# Exposure_Timer.net
KiCad netlist of a schematic drawn in EAGLE
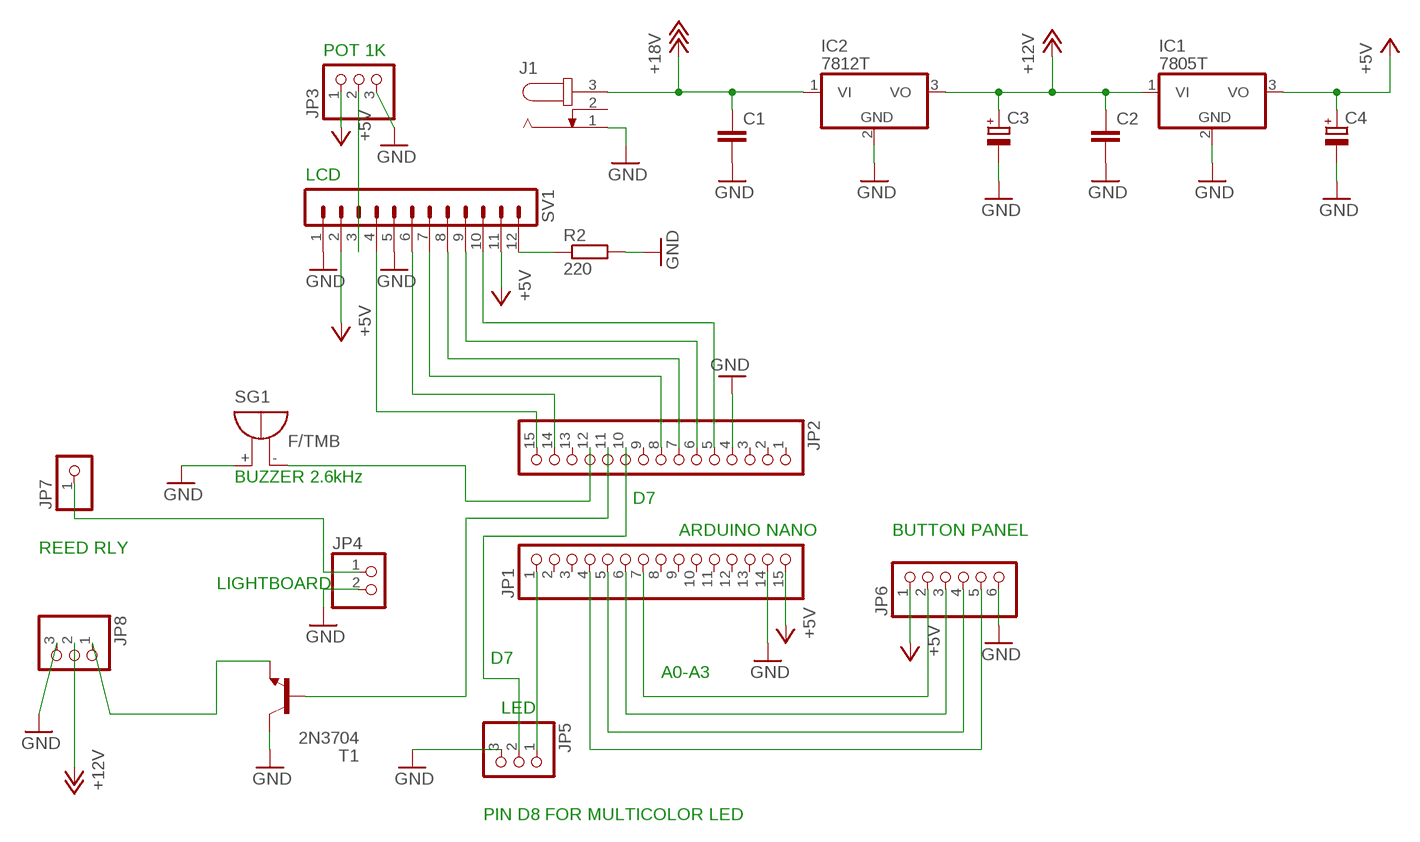
[diagram p0: schematic, sheet 1]

(export (version "E")
  (design (tool "Eeschema 10.0.6"))
  (components
    (comp (ref "C1")
      (value "C-EU025-030X050")
      (footprint "eagle-import:C025-030X050")
      (libsource (lib "eagle-import") (part "C-EU025-030X050"))
    )
    (comp (ref "C2")
      (value "C-EU025-030X050")
      (footprint "eagle-import:C025-030X050")
      (libsource (lib "eagle-import") (part "C-EU025-030X050"))
    )
    (comp (ref "C3")
      (value "CPOL-EUE2,5-6E")
      (footprint "eagle-import:E2,5-6E")
      (libsource (lib "eagle-import") (part "CPOL-EUE2,5-6E"))
    )
    (comp (ref "C4")
      (value "CPOL-EUE2,5-6E")
      (footprint "eagle-import:E2,5-6E")
      (libsource (lib "eagle-import") (part "CPOL-EUE2,5-6E"))
    )
    (comp (ref "IC1")
      (value "7805T")
      (footprint "eagle-import:TO220H")
      (libsource (lib "eagle-import") (part "78T05"))
    )
    (comp (ref "IC2")
      (value "7812T")
      (footprint "eagle-import:TO220H")
      (libsource (lib "eagle-import") (part "78T12"))
    )
    (comp (ref "J1")
      (value "JACK-PLUG1")
      (footprint "eagle-import:SPC4078")
      (libsource (lib "eagle-import") (part "JACK-PLUG1"))
    )
    (comp (ref "JP1")
      (value "PINHD-1X15")
      (footprint "eagle-import:1X15")
      (libsource (lib "eagle-import") (part "PINHD-1X15"))
    )
    (comp (ref "JP2")
      (value "PINHD-1X15")
      (footprint "eagle-import:1X15")
      (libsource (lib "eagle-import") (part "PINHD-1X15"))
    )
    (comp (ref "JP3")
      (value "PINHD-1X3")
      (footprint "eagle-import:1X03")
      (libsource (lib "eagle-import") (part "PINHD-1X3"))
    )
    (comp (ref "JP4")
      (value "PINHD-1X2")
      (footprint "eagle-import:1X02")
      (libsource (lib "eagle-import") (part "PINHD-1X2"))
    )
    (comp (ref "JP5")
      (value "PINHD-1X3")
      (footprint "eagle-import:1X03")
      (libsource (lib "eagle-import") (part "PINHD-1X3"))
    )
    (comp (ref "JP6")
      (value "PINHD-1X6")
      (footprint "eagle-import:1X06")
      (libsource (lib "eagle-import") (part "PINHD-1X6"))
    )
    (comp (ref "JP7")
      (value "PINHD-1X1")
      (footprint "eagle-import:1X01")
      (libsource (lib "eagle-import") (part "PINHD-1X1"))
    )
    (comp (ref "JP8")
      (value "PINHD-1X3")
      (footprint "eagle-import:1X03")
      (libsource (lib "eagle-import") (part "PINHD-1X3"))
    )
    (comp (ref "R2")
      (value "220")
      (footprint "eagle-import:0204_7")
      (libsource (lib "eagle-import") (part "R-EU_0204/7"))
    )
    (comp (ref "SG1")
      (value "F/TMB")
      (footprint "eagle-import:F_TMB")
      (libsource (lib "eagle-import") (part "F/TMB"))
    )
    (comp (ref "SV1")
      (value "MA12-1")
      (footprint "eagle-import:MA12-1")
      (libsource (lib "eagle-import") (part "MA12-1"))
    )
    (comp (ref "T1")
      (value "2N3704")
      (footprint "eagle-import:TO92")
      (libsource (lib "eagle-import") (part "2N3704"))
    )
  )
  (nets
    (net (code "1") (name "+5V") (class "Default")
      (node (ref "C4") (pin "+") (pinfunction "+_+") (pintype "passive"))
      (node (ref "IC1") (pin "3") (pinfunction "VO_3") (pintype "passive"))
      (node (ref "JP1") (pin "15") (pinfunction "15_15") (pintype "passive"))
      (node (ref "JP3") (pin "1") (pinfunction "1_1") (pintype "passive"))
      (node (ref "JP6") (pin "1") (pinfunction "1_1") (pintype "passive"))
      (node (ref "SV1") (pin "11") (pinfunction "11_11") (pintype "passive"))
      (node (ref "SV1") (pin "2") (pinfunction "2_2") (pintype "passive"))
    )
    (net (code "2") (name "+12V") (class "Default")
      (node (ref "C2") (pin "1") (pinfunction "1_1") (pintype "passive"))
      (node (ref "C3") (pin "+") (pinfunction "+_+") (pintype "passive"))
      (node (ref "IC1") (pin "1") (pinfunction "VI_1") (pintype "input"))
      (node (ref "IC2") (pin "3") (pinfunction "VO_3") (pintype "passive"))
      (node (ref "JP8") (pin "2") (pinfunction "2_2") (pintype "passive"))
    )
    (net (code "3") (name "+18V") (class "Default")
      (node (ref "C1") (pin "1") (pinfunction "1_1") (pintype "passive"))
      (node (ref "IC2") (pin "1") (pinfunction "VI_1") (pintype "input"))
      (node (ref "J1") (pin "3") (pinfunction "3_3") (pintype "passive"))
    )
    (net (code "4") (name "GND") (class "Default")
      (node (ref "C1") (pin "2") (pinfunction "2_2") (pintype "passive"))
      (node (ref "C2") (pin "2") (pinfunction "2_2") (pintype "passive"))
      (node (ref "C3") (pin "-") (pinfunction "-_-") (pintype "passive"))
      (node (ref "C4") (pin "-") (pinfunction "-_-") (pintype "passive"))
      (node (ref "IC1") (pin "2") (pinfunction "GND_2") (pintype "passive"))
      (node (ref "IC2") (pin "2") (pinfunction "GND_2") (pintype "passive"))
      (node (ref "J1") (pin "1") (pinfunction "1_1") (pintype "passive"))
      (node (ref "JP1") (pin "14") (pinfunction "14_14") (pintype "passive"))
      (node (ref "JP2") (pin "4") (pinfunction "4_4") (pintype "passive"))
      (node (ref "JP3") (pin "3") (pinfunction "3_3") (pintype "passive"))
      (node (ref "JP4") (pin "2") (pinfunction "2_2") (pintype "passive"))
      (node (ref "JP5") (pin "3") (pinfunction "3_3") (pintype "passive"))
      (node (ref "JP6") (pin "6") (pinfunction "6_6") (pintype "passive"))
      (node (ref "JP8") (pin "3") (pinfunction "3_3") (pintype "passive"))
      (node (ref "R2") (pin "2") (pinfunction "2_2") (pintype "passive"))
      (node (ref "SG1") (pin "+") (pinfunction "+_+") (pintype "passive"))
      (node (ref "SV1") (pin "1") (pinfunction "1_1") (pintype "passive"))
      (node (ref "SV1") (pin "5") (pinfunction "5_5") (pintype "passive"))
      (node (ref "T1") (pin "2") (pinfunction "C_2") (pintype "passive"))
    )
    (net (code "5") (name "Net-(JP1-Pad1)") (class "Default")
      (node (ref "JP1") (pin "1") (pinfunction "1_1") (pintype "passive"))
      (node (ref "JP5") (pin "1") (pinfunction "1_1") (pintype "passive"))
    )
    (net (code "6") (name "Net-(JP1-Pad4)") (class "Default")
      (node (ref "JP1") (pin "4") (pinfunction "4_4") (pintype "passive"))
      (node (ref "JP6") (pin "5") (pinfunction "5_5") (pintype "passive"))
    )
    (net (code "7") (name "Net-(JP1-Pad5)") (class "Default")
      (node (ref "JP1") (pin "5") (pinfunction "5_5") (pintype "passive"))
      (node (ref "JP6") (pin "4") (pinfunction "4_4") (pintype "passive"))
    )
    (net (code "8") (name "Net-(JP1-Pad6)") (class "Default")
      (node (ref "JP1") (pin "6") (pinfunction "6_6") (pintype "passive"))
      (node (ref "JP6") (pin "3") (pinfunction "3_3") (pintype "passive"))
    )
    (net (code "9") (name "Net-(JP1-Pad7)") (class "Default")
      (node (ref "JP1") (pin "7") (pinfunction "7_7") (pintype "passive"))
      (node (ref "JP6") (pin "2") (pinfunction "2_2") (pintype "passive"))
    )
    (net (code "10") (name "Net-(JP2-Pad5)") (class "Default")
      (node (ref "JP2") (pin "5") (pinfunction "5_5") (pintype "passive"))
      (node (ref "SV1") (pin "10") (pinfunction "10_10") (pintype "passive"))
    )
    (net (code "11") (name "Net-(JP2-Pad6)") (class "Default")
      (node (ref "JP2") (pin "6") (pinfunction "6_6") (pintype "passive"))
      (node (ref "SV1") (pin "9") (pinfunction "9_9") (pintype "passive"))
    )
    (net (code "12") (name "Net-(JP2-Pad7)") (class "Default")
      (node (ref "JP2") (pin "7") (pinfunction "7_7") (pintype "passive"))
      (node (ref "SV1") (pin "8") (pinfunction "8_8") (pintype "passive"))
    )
    (net (code "13") (name "Net-(JP2-Pad8)") (class "Default")
      (node (ref "JP2") (pin "8") (pinfunction "8_8") (pintype "passive"))
      (node (ref "SV1") (pin "7") (pinfunction "7_7") (pintype "passive"))
    )
    (net (code "14") (name "Net-(JP2-Pad10)") (class "Default")
      (node (ref "JP2") (pin "10") (pinfunction "10_10") (pintype "passive"))
      (node (ref "JP5") (pin "2") (pinfunction "2_2") (pintype "passive"))
    )
    (net (code "15") (name "Net-(JP2-Pad12)") (class "Default")
      (node (ref "JP2") (pin "12") (pinfunction "12_12") (pintype "passive"))
      (node (ref "SG1") (pin "-") (pinfunction "-_-") (pintype "passive"))
    )
    (net (code "16") (name "Net-(JP2-Pad14)") (class "Default")
      (node (ref "JP2") (pin "14") (pinfunction "14_14") (pintype "passive"))
      (node (ref "SV1") (pin "6") (pinfunction "6_6") (pintype "passive"))
    )
    (net (code "17") (name "Net-(JP2-Pad15)") (class "Default")
      (node (ref "JP2") (pin "15") (pinfunction "15_15") (pintype "passive"))
      (node (ref "SV1") (pin "4") (pinfunction "4_4") (pintype "passive"))
    )
    (net (code "18") (name "Net-(JP3-Pad2)") (class "Default")
      (node (ref "JP3") (pin "2") (pinfunction "2_2") (pintype "passive"))
      (node (ref "SV1") (pin "3") (pinfunction "3_3") (pintype "passive"))
    )
    (net (code "19") (name "Net-(JP4-Pad1)") (class "Default")
      (node (ref "JP4") (pin "1") (pinfunction "1_1") (pintype "passive"))
      (node (ref "JP7") (pin "1") (pinfunction "1_1") (pintype "passive"))
    )
    (net (code "20") (name "Net-(R2-Pad1)") (class "Default")
      (node (ref "R2") (pin "1") (pinfunction "1_1") (pintype "passive"))
      (node (ref "SV1") (pin "12") (pinfunction "12_12") (pintype "passive"))
    )
    (net (code "21") (name "Net-(T1-B)") (class "Default")
      (node (ref "JP2") (pin "11") (pinfunction "11_11") (pintype "passive"))
      (node (ref "T1") (pin "1") (pinfunction "B_1") (pintype "passive"))
    )
    (net (code "22") (name "Net-(T1-E)") (class "Default")
      (node (ref "JP8") (pin "1") (pinfunction "1_1") (pintype "passive"))
      (node (ref "T1") (pin "3") (pinfunction "E_3") (pintype "passive"))
    )
    (net (code "23") (name "unconnected-(J1-Pad2)") (class "Default")
      (node (ref "J1") (pin "2") (pinfunction "2_2") (pintype "passive"))
    )
    (net (code "24") (name "unconnected-(JP1-Pad2)") (class "Default")
      (node (ref "JP1") (pin "2") (pinfunction "2_2") (pintype "passive"))
    )
    (net (code "25") (name "unconnected-(JP1-Pad3)") (class "Default")
      (node (ref "JP1") (pin "3") (pinfunction "3_3") (pintype "passive"))
    )
    (net (code "26") (name "unconnected-(JP1-Pad8)") (class "Default")
      (node (ref "JP1") (pin "8") (pinfunction "8_8") (pintype "passive"))
    )
    (net (code "27") (name "unconnected-(JP1-Pad9)") (class "Default")
      (node (ref "JP1") (pin "9") (pinfunction "9_9") (pintype "passive"))
    )
    (net (code "28") (name "unconnected-(JP1-Pad10)") (class "Default")
      (node (ref "JP1") (pin "10") (pinfunction "10_10") (pintype "passive"))
    )
    (net (code "29") (name "unconnected-(JP1-Pad11)") (class "Default")
      (node (ref "JP1") (pin "11") (pinfunction "11_11") (pintype "passive"))
    )
    (net (code "30") (name "unconnected-(JP1-Pad12)") (class "Default")
      (node (ref "JP1") (pin "12") (pinfunction "12_12") (pintype "passive"))
    )
    (net (code "31") (name "unconnected-(JP1-Pad13)") (class "Default")
      (node (ref "JP1") (pin "13") (pinfunction "13_13") (pintype "passive"))
    )
    (net (code "32") (name "unconnected-(JP2-Pad1)") (class "Default")
      (node (ref "JP2") (pin "1") (pinfunction "1_1") (pintype "passive"))
    )
    (net (code "33") (name "unconnected-(JP2-Pad2)") (class "Default")
      (node (ref "JP2") (pin "2") (pinfunction "2_2") (pintype "passive"))
    )
    (net (code "34") (name "unconnected-(JP2-Pad3)") (class "Default")
      (node (ref "JP2") (pin "3") (pinfunction "3_3") (pintype "passive"))
    )
    (net (code "35") (name "unconnected-(JP2-Pad9)") (class "Default")
      (node (ref "JP2") (pin "9") (pinfunction "9_9") (pintype "passive"))
    )
    (net (code "36") (name "unconnected-(JP2-Pad13)") (class "Default")
      (node (ref "JP2") (pin "13") (pinfunction "13_13") (pintype "passive"))
    )
  )
)
